# can_tcan1462v.net
KiCad netlist of a schematic drawn in Altium Designer
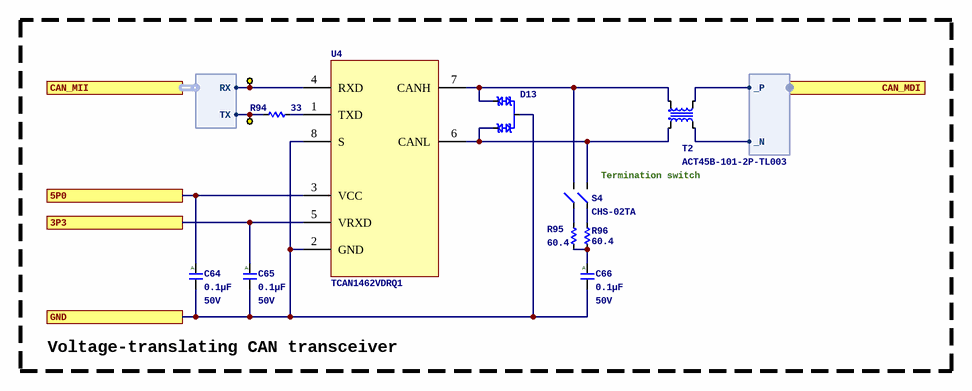
[diagram p0: can_tcan1462v.SchDoc]

(export (version "E")
  (design (tool "Eeschema 10.0.6"))
  (components
    (comp (ref "C64")
      (value "CGA2B3X7R1H104M050BB")
      (footprint "C0402_0.55MM")
      (description "CAP CER 0.1UF 50V X7R 0402")
      (fields
        (field (name "CAPACITANCE") "0.1µF")
        (field (name "VOLTAGE - RATED") "50V")
        (field (name "TOLERANCE") "±20%")
        (field (name "MANUFACTURER") "TDK Corporation")
      )
      (libsource (lib "sscp") (part "__template_cap_auto"))
    )
    (comp (ref "C65")
      (value "CGA2B3X7R1H104M050BB")
      (footprint "C0402_0.55MM")
      (description "CAP CER 0.1UF 50V X7R 0402")
      (fields
        (field (name "CAPACITANCE") "0.1µF")
        (field (name "VOLTAGE - RATED") "50V")
        (field (name "TOLERANCE") "±20%")
        (field (name "MANUFACTURER") "TDK Corporation")
      )
      (libsource (lib "sscp") (part "__template_cap_auto"))
    )
    (comp (ref "C66")
      (value "CGA2B3X7R1H104M050BB")
      (footprint "C0402_0.55MM")
      (description "CAP CER 0.1UF 50V X7R 0402")
      (fields
        (field (name "CAPACITANCE") "0.1µF")
        (field (name "VOLTAGE - RATED") "50V")
        (field (name "TOLERANCE") "±20%")
        (field (name "MANUFACTURER") "TDK Corporation")
      )
      (libsource (lib "sscp") (part "__template_cap_auto"))
    )
    (comp (ref "D13")
      (value "PESD2CAN,215")
      (footprint "3SOT23")
      (description "DIODE ESD CAN SOT-23")
      (fields (field (name "MANUFACTURER") "NXP Semiconductors"))
      (libsource (lib "SSCP") (part "TVS_PESD2CAN"))
    )
    (comp (ref "R94")
      (value "ERJ-2RKF33R0X")
      (footprint "R0402_0.40MM")
      (description "RES SMD 33 OHM 1% 1/10W 0402")
      (fields
        (field (name "RESISTANCE") "33")
        (field (name "TOLERANCE") "±1%")
        (field (name "MANUFACTURER") "Panasonic Electronic Components")
      )
      (libsource (lib "sscp") (part "__template_resistor"))
    )
    (comp (ref "R95")
      (value "ERJ-2RKF60R4X")
      (footprint "R0402_0.40MM")
      (description "RES SMD 60.4 OHM 1% 1/10W 0402")
      (fields
        (field (name "RESISTANCE") "60.4")
        (field (name "TOLERANCE") "±1%")
        (field (name "MANUFACTURER") "Panasonic Electronic Components")
      )
      (libsource (lib "sscp") (part "__template_resistor"))
    )
    (comp (ref "R96")
      (value "ERJ-2RKF60R4X")
      (footprint "R0402_0.40MM")
      (description "RES SMD 60.4 OHM 1% 1/10W 0402")
      (fields
        (field (name "RESISTANCE") "60.4")
        (field (name "TOLERANCE") "±1%")
        (field (name "MANUFACTURER") "Panasonic Electronic Components")
      )
      (libsource (lib "sscp") (part "__template_resistor"))
    )
    (comp (ref "S4")
      (value "CHS-02TA")
      (footprint "SWITCH_NIDEC_CHS-02TA")
      (description "DIP Switch, Slide, SPST, Flush, Recessed, 6VDC, 100mA, CHS Series ¦ Nidec Components CHS-02TA")
      (fields (field (name "MANUFACTURER") "Nidec Copal"))
      (libsource (lib "SSCP") (part "SWITCH_CHS-02TA"))
    )
    (comp (ref "T2")
      (value "CHOKE_ACT45B-101-2P-TL003")
      (footprint "CHOKE_ACT45B-101-2P-TL003")
      (description "CHOKE COMMON MODE 5000 OHM SMD")
      (fields
        (field (name "MANUFACTURER") "TDK Corporation")
        (field (name "MANUFACTURER PART NUMBER") "ACT45B-101-2P-TL003")
      )
      (libsource (lib "SSCP") (part "CHOKE_ACT45B-101-2P-TL003"))
    )
    (comp (ref "TP3")
      (value "~")
      (footprint "TP_GRABBY")
      (description "EMBEDDED TEST POINT FOR SALEAE TEST CLIPS")
      (libsource (lib "SSCP") (part "TEST_GRABBER"))
    )
    (comp (ref "TP4")
      (value "~")
      (footprint "TP_GRABBY")
      (description "EMBEDDED TEST POINT FOR SALEAE TEST CLIPS")
      (libsource (lib "SSCP") (part "TEST_GRABBER"))
    )
    (comp (ref "U4")
      (value "TCAN1462VDRQ1")
      (footprint "8SOIC150")
      (description "Automotive signal improvement CAN FD transceiver with VIO and standby 8-SOIC -40 to 125")
      (fields (field (name "MANUFACTURER") "Texas Instruments"))
      (libsource (lib "SSCP") (part "CAN_TCAN1462VDRQ1"))
    )
  )
  (nets
    (net (code "3") (name "/3P3") (class "Default")
      (node (ref "C65") (pin "1") (pintype "passive"))
      (node (ref "U4") (pin "5") (pinfunction "VRXD_5") (pintype "passive"))
    )
    (net (code "4") (name "/5P0") (class "Default")
      (node (ref "C64") (pin "1") (pintype "passive"))
      (node (ref "U4") (pin "3") (pinfunction "VCC_3") (pintype "passive"))
    )
    (net (code "5") (name "/GND") (class "Default")
      (node (ref "C64") (pin "2") (pintype "passive"))
      (node (ref "C65") (pin "2") (pintype "passive"))
      (node (ref "C66") (pin "2") (pintype "passive"))
      (node (ref "D13") (pin "3") (pintype "passive"))
      (node (ref "U4") (pin "2") (pinfunction "GND_2") (pintype "passive"))
      (node (ref "U4") (pin "8") (pinfunction "S_8") (pintype "passive"))
    )
    (net (code "6") (name "/RX") (class "Default")
      (node (ref "TP3") (pin "1") (pintype "passive"))
      (node (ref "U4") (pin "4") (pinfunction "RXD_4") (pintype "passive"))
    )
    (net (code "7") (name "/TX") (class "Default")
      (node (ref "R94") (pin "1") (pintype "passive"))
      (node (ref "TP4") (pin "1") (pintype "passive"))
    )
    (net (code "8") (name "/_N") (class "Default") (node (ref "T2") (pin "4") (pintype "passive")))
    (net (code "9") (name "/_P") (class "Default") (node (ref "T2") (pin "3") (pintype "passive")))
    (net (code "12") (name "Net-(C66-Pad1)") (class "Default")
      (node (ref "C66") (pin "1") (pintype "passive"))
      (node (ref "R95") (pin "2") (pintype "passive"))
      (node (ref "R96") (pin "1") (pintype "passive"))
    )
    (net (code "13") (name "Net-(R95-Pad1)") (class "Default")
      (node (ref "R95") (pin "1") (pintype "passive"))
      (node (ref "S4") (pin "1") (pintype "passive"))
    )
    (net (code "14") (name "Net-(R96-Pad2)") (class "Default")
      (node (ref "R96") (pin "2") (pintype "passive"))
      (node (ref "S4") (pin "3") (pintype "passive"))
    )
    (net (code "15") (name "Net-(U4-CANH)") (class "Default")
      (node (ref "D13") (pin "1") (pintype "passive"))
      (node (ref "S4") (pin "2") (pintype "passive"))
      (node (ref "T2") (pin "2") (pintype "passive"))
      (node (ref "U4") (pin "7") (pinfunction "CANH_7") (pintype "passive"))
    )
    (net (code "16") (name "Net-(U4-CANL)") (class "Default")
      (node (ref "D13") (pin "2") (pintype "passive"))
      (node (ref "S4") (pin "4") (pintype "passive"))
      (node (ref "T2") (pin "1") (pintype "passive"))
      (node (ref "U4") (pin "6") (pinfunction "CANL_6") (pintype "passive"))
    )
    (net (code "17") (name "Net-(U4-TXD)") (class "Default")
      (node (ref "R94") (pin "2") (pintype "passive"))
      (node (ref "U4") (pin "1") (pinfunction "TXD_1") (pintype "passive"))
    )
  )
)
